# Infrarouge_R_T_LED_SMD.net
KiCad netlist of a schematic drawn in Altium Designer
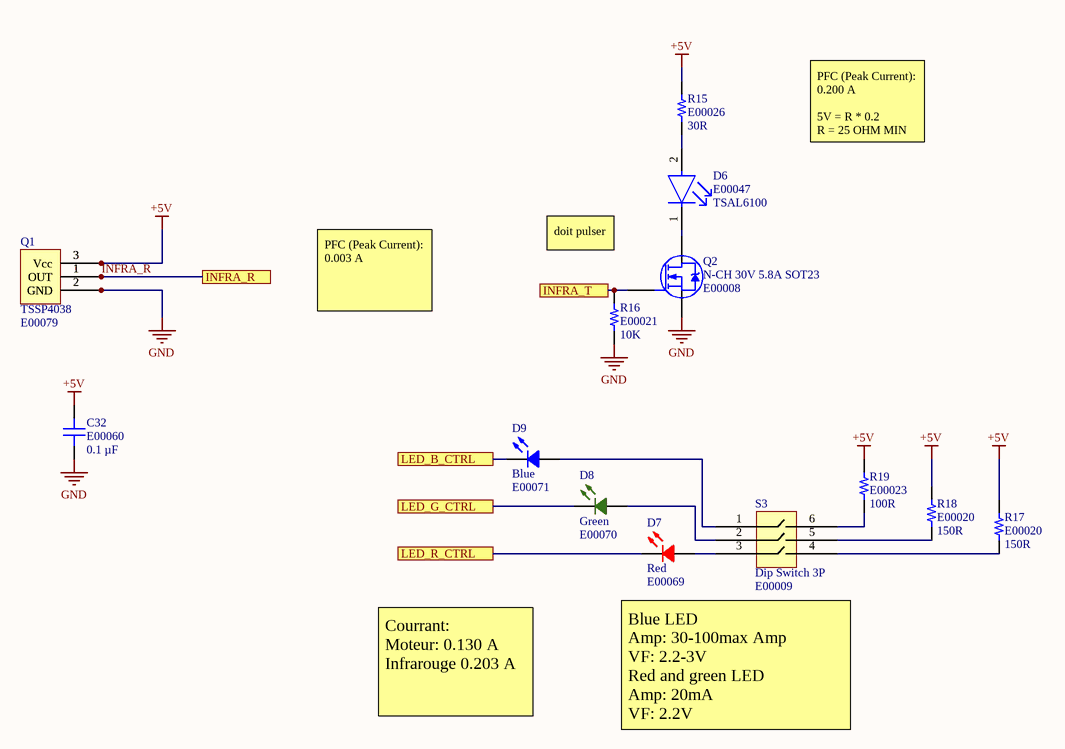
[diagram p0: Infrarouge R&T, LED SMD.SchDoc]

(export (version "E")
  (design (tool "Eeschema 10.0.6"))
  (components
    (comp (ref "C32")
      (value "0.1 µF")
      (footprint "CAP 0603")
      (description "CAP CER 0.1UF 50V X7R 0603")
      (fields
        (field (name "MANUFACTURER") "KEMET")
        (field (name "TOLERANCE") "±10%")
        (field (name "ADAM INVENTORY NUMBER 1") "E00060")
      )
      (libsource (lib "ADAM LIBRARY") (part "CAP CER 0.1UF 50V X7R 0603"))
    )
    (comp (ref "D6")
      (value "TSAL6100")
      (footprint "IR TRANSMITTER")
      (description "Infrared (IR) Emitter 940nm 1.35V 100mA 80mW/sr @ 100mA 20° Radial, 5mm Dia (T 1 3/4)")
      (fields
        (field (name "ADAM INVENTORY NUMBER 1") "E00047")
        (field (name "MANUFACTURER PART NUMBER 1") "TSAL6100")
      )
      (libsource (lib "ADAM LIBRARY") (part "TSAL6100"))
    )
    (comp (ref "D7")
      (value "Red")
      (footprint "Red Led 0603")
      (description "0603 RED LED")
      (fields
        (field (name "MANUFACTURER") "American Bright Optoelectronics Corporation")
        (field (name "ADAM INVENTORY NUMBER 1") "E00069")
      )
      (libsource (lib "ADAM LIBRARY") (part "0603 RED LED"))
    )
    (comp (ref "D8")
      (value "Green")
      (footprint "Green LED 0603")
      (description "LED GREEN 0603 SMD")
      (fields (field (name "MANUFACTURER") "Dialight") (field (name "ADAM INVENTORY NUMBER 1") "E00070"))
      (libsource (lib "ADAM LIBRARY") (part "0603 GREEN LED"))
    )
    (comp (ref "D9")
      (value "Blue")
      (footprint "Blue LED 0603")
      (description "Blue 470nm LED Indication - Discrete 3.3V 0603 (1608 Metric)")
      (fields (field (name "ADAM INVENTORY NUMBER 1") "E00071"))
      (libsource (lib "ADAM LIBRARY") (part "0603 BLUE LED"))
    )
    (comp (ref "Q1")
      (value "TSSP4038")
      (footprint "IR Receptor")
      (description "Remote Receiver Sensor 38.0kHz 45m Through Hole")
      (fields (field (name "ADAM INVENTORY NUMBER 1") "E00079"))
      (libsource (lib "ADAM LIBRARY") (part "TSSP4038IR Sensor"))
    )
    (comp (ref "Q2")
      (value "N-CH 30V 5.8A SOT23")
      (footprint "N-CHANNEL TRANS")
      (description "N-Channel 5.8A (Tj) 350mW Surface Mount SOT-23")
      (fields (field (name "MANUFACTURER") "MCC") (field (name "ADAM INVENTORY NUMBER 1") "E00008"))
      (libsource (lib "ADAM LIBRARY") (part "TRANS N-CHANNEL 30V 5.8A SOT23"))
    )
    (comp (ref "R15")
      (value "30R")
      (footprint "RES 0603")
      (description "RES 30 OHM 1% 1/3W 0603")
      (fields
        (field (name "MANUFACTURER") "KOA Speer Electronics, Inc.")
        (field (name "TOLERANCE") "±1%")
        (field (name "ADAM INVENTORY NUMBER 1") "E00026")
      )
      (libsource (lib "ADAM LIBRARY") (part "RES SMD 30 OHM"))
    )
    (comp (ref "R16")
      (value "10K")
      (footprint "RES 0603")
      (description "RES SMD 10K OHM 1% 1/10W 0603")
      (fields
        (field (name "MANUFACTURER") "Rohm Semiconductor")
        (field (name "TOLERANCE") "±1%")
        (field (name "ADAM INVENTORY NUMBER 1") "E00021")
      )
      (libsource (lib "ADAM LIBRARY") (part "RES SMD 10K OHM"))
    )
    (comp (ref "R17")
      (value "150R")
      (footprint "RES 0603")
      (description "RES SMD 150 OHM 0.1% 1/8W 0603")
      (fields
        (field (name "MANUFACTURER") "Vishay Beyschlag")
        (field (name "TOLERANCE") "±0.1%")
        (field (name "ADAM INVENTORY NUMBER 1") "E00020")
      )
      (libsource (lib "ADAM LIBRARY") (part "RES SMD 150 OHM"))
    )
    (comp (ref "R18")
      (value "150R")
      (footprint "RES 0603")
      (description "RES SMD 150 OHM 0.1% 1/8W 0603")
      (fields
        (field (name "MANUFACTURER") "Vishay Beyschlag")
        (field (name "TOLERANCE") "±0.1%")
        (field (name "ADAM INVENTORY NUMBER 1") "E00020")
      )
      (libsource (lib "ADAM LIBRARY") (part "RES SMD 150 OHM"))
    )
    (comp (ref "R19")
      (value "100R")
      (footprint "RES 0603")
      (description "RESISTOR 100 Ohm SMD 1% 1/10W")
      (fields
        (field (name "MANUFACTURER") "Yageo")
        (field (name "TOLERANCE") "±1%")
        (field (name "ADAM INVENTORY NUMBER 1") "E00023")
      )
      (libsource (lib "ADAM LIBRARY") (part "RES SMD 100 OHM"))
    )
    (comp (ref "S3")
      (value "Dip Switch 3P")
      (footprint "DIPSWITCH SMD 3P")
      (description "Dip Switch SPST 3 Position Surface Mount Slide (Standard) Actuator 25mA 24VDC")
      (fields (field (name "MANUFACTURER") "CUI") (field (name "ADAM INVENTORY NUMBER 1") "E00009"))
      (libsource (lib "ADAM LIBRARY") (part "Dip Switch 3P"))
    )
  )
  (nets
    (net (code "1") (name "+5V") (class "Default")
      (node (ref "C32") (pin "2") (pinfunction "2_2") (pintype "passive"))
      (node (ref "Q1") (pin "3") (pinfunction "Vcc_3") (pintype "passive"))
      (node (ref "R15") (pin "2") (pinfunction "2_2") (pintype "passive"))
      (node (ref "R17") (pin "2") (pinfunction "2_2") (pintype "passive"))
      (node (ref "R18") (pin "2") (pinfunction "2_2") (pintype "passive"))
      (node (ref "R19") (pin "2") (pinfunction "2_2") (pintype "passive"))
    )
    (net (code "2") (name "/INFRA_R") (class "Default")
      (node (ref "Q1") (pin "1") (pinfunction "OUT_1") (pintype "passive"))
    )
    (net (code "3") (name "/INFRA_T") (class "Default")
      (node (ref "Q2") (pin "1") (pinfunction "G_1") (pintype "passive"))
      (node (ref "R16") (pin "2") (pinfunction "2_2") (pintype "passive"))
    )
    (net (code "4") (name "/LED_B_CTRL") (class "Default")
      (node (ref "D9") (pin "2") (pinfunction "2_2") (pintype "passive"))
    )
    (net (code "5") (name "/LED_G_CTRL") (class "Default")
      (node (ref "D8") (pin "2") (pinfunction "2_2") (pintype "passive"))
    )
    (net (code "6") (name "/LED_R_CTRL") (class "Default")
      (node (ref "D7") (pin "2") (pinfunction "2_2") (pintype "passive"))
    )
    (net (code "7") (name "GND") (class "Default")
      (node (ref "C32") (pin "1") (pinfunction "1_1") (pintype "passive"))
      (node (ref "Q1") (pin "2") (pinfunction "GND_2") (pintype "passive"))
      (node (ref "Q2") (pin "2") (pinfunction "S_2") (pintype "passive"))
      (node (ref "R16") (pin "1") (pinfunction "1_1") (pintype "passive"))
    )
    (net (code "8") (name "Net-(D6-A)") (class "Default")
      (node (ref "D6") (pin "2") (pinfunction "A_2") (pintype "passive"))
      (node (ref "R15") (pin "1") (pinfunction "1_1") (pintype "passive"))
    )
    (net (code "9") (name "Net-(D6-C)") (class "Default")
      (node (ref "D6") (pin "1") (pinfunction "C_1") (pintype "passive"))
      (node (ref "Q2") (pin "3") (pinfunction "D_3") (pintype "passive"))
    )
    (net (code "10") (name "Net-(D7-Pad1)") (class "Default")
      (node (ref "D7") (pin "1") (pinfunction "1_1") (pintype "passive"))
      (node (ref "S3") (pin "3") (pinfunction "3_3") (pintype "passive"))
    )
    (net (code "11") (name "Net-(D8-Pad1)") (class "Default")
      (node (ref "D8") (pin "1") (pinfunction "1_1") (pintype "passive"))
      (node (ref "S3") (pin "2") (pinfunction "2_2") (pintype "passive"))
    )
    (net (code "12") (name "Net-(D9-Pad1)") (class "Default")
      (node (ref "D9") (pin "1") (pinfunction "1_1") (pintype "passive"))
      (node (ref "S3") (pin "1") (pinfunction "1_1") (pintype "passive"))
    )
    (net (code "13") (name "Net-(R17-Pad1)") (class "Default")
      (node (ref "R17") (pin "1") (pinfunction "1_1") (pintype "passive"))
      (node (ref "S3") (pin "4") (pinfunction "4_4") (pintype "passive"))
    )
    (net (code "14") (name "Net-(R18-Pad1)") (class "Default")
      (node (ref "R18") (pin "1") (pinfunction "1_1") (pintype "passive"))
      (node (ref "S3") (pin "5") (pinfunction "5_5") (pintype "passive"))
    )
    (net (code "15") (name "Net-(R19-Pad1)") (class "Default")
      (node (ref "R19") (pin "1") (pinfunction "1_1") (pintype "passive"))
      (node (ref "S3") (pin "6") (pinfunction "6_6") (pintype "passive"))
    )
  )
)
